# mimic1705.net
KiCad netlist of a schematic drawn in EAGLE
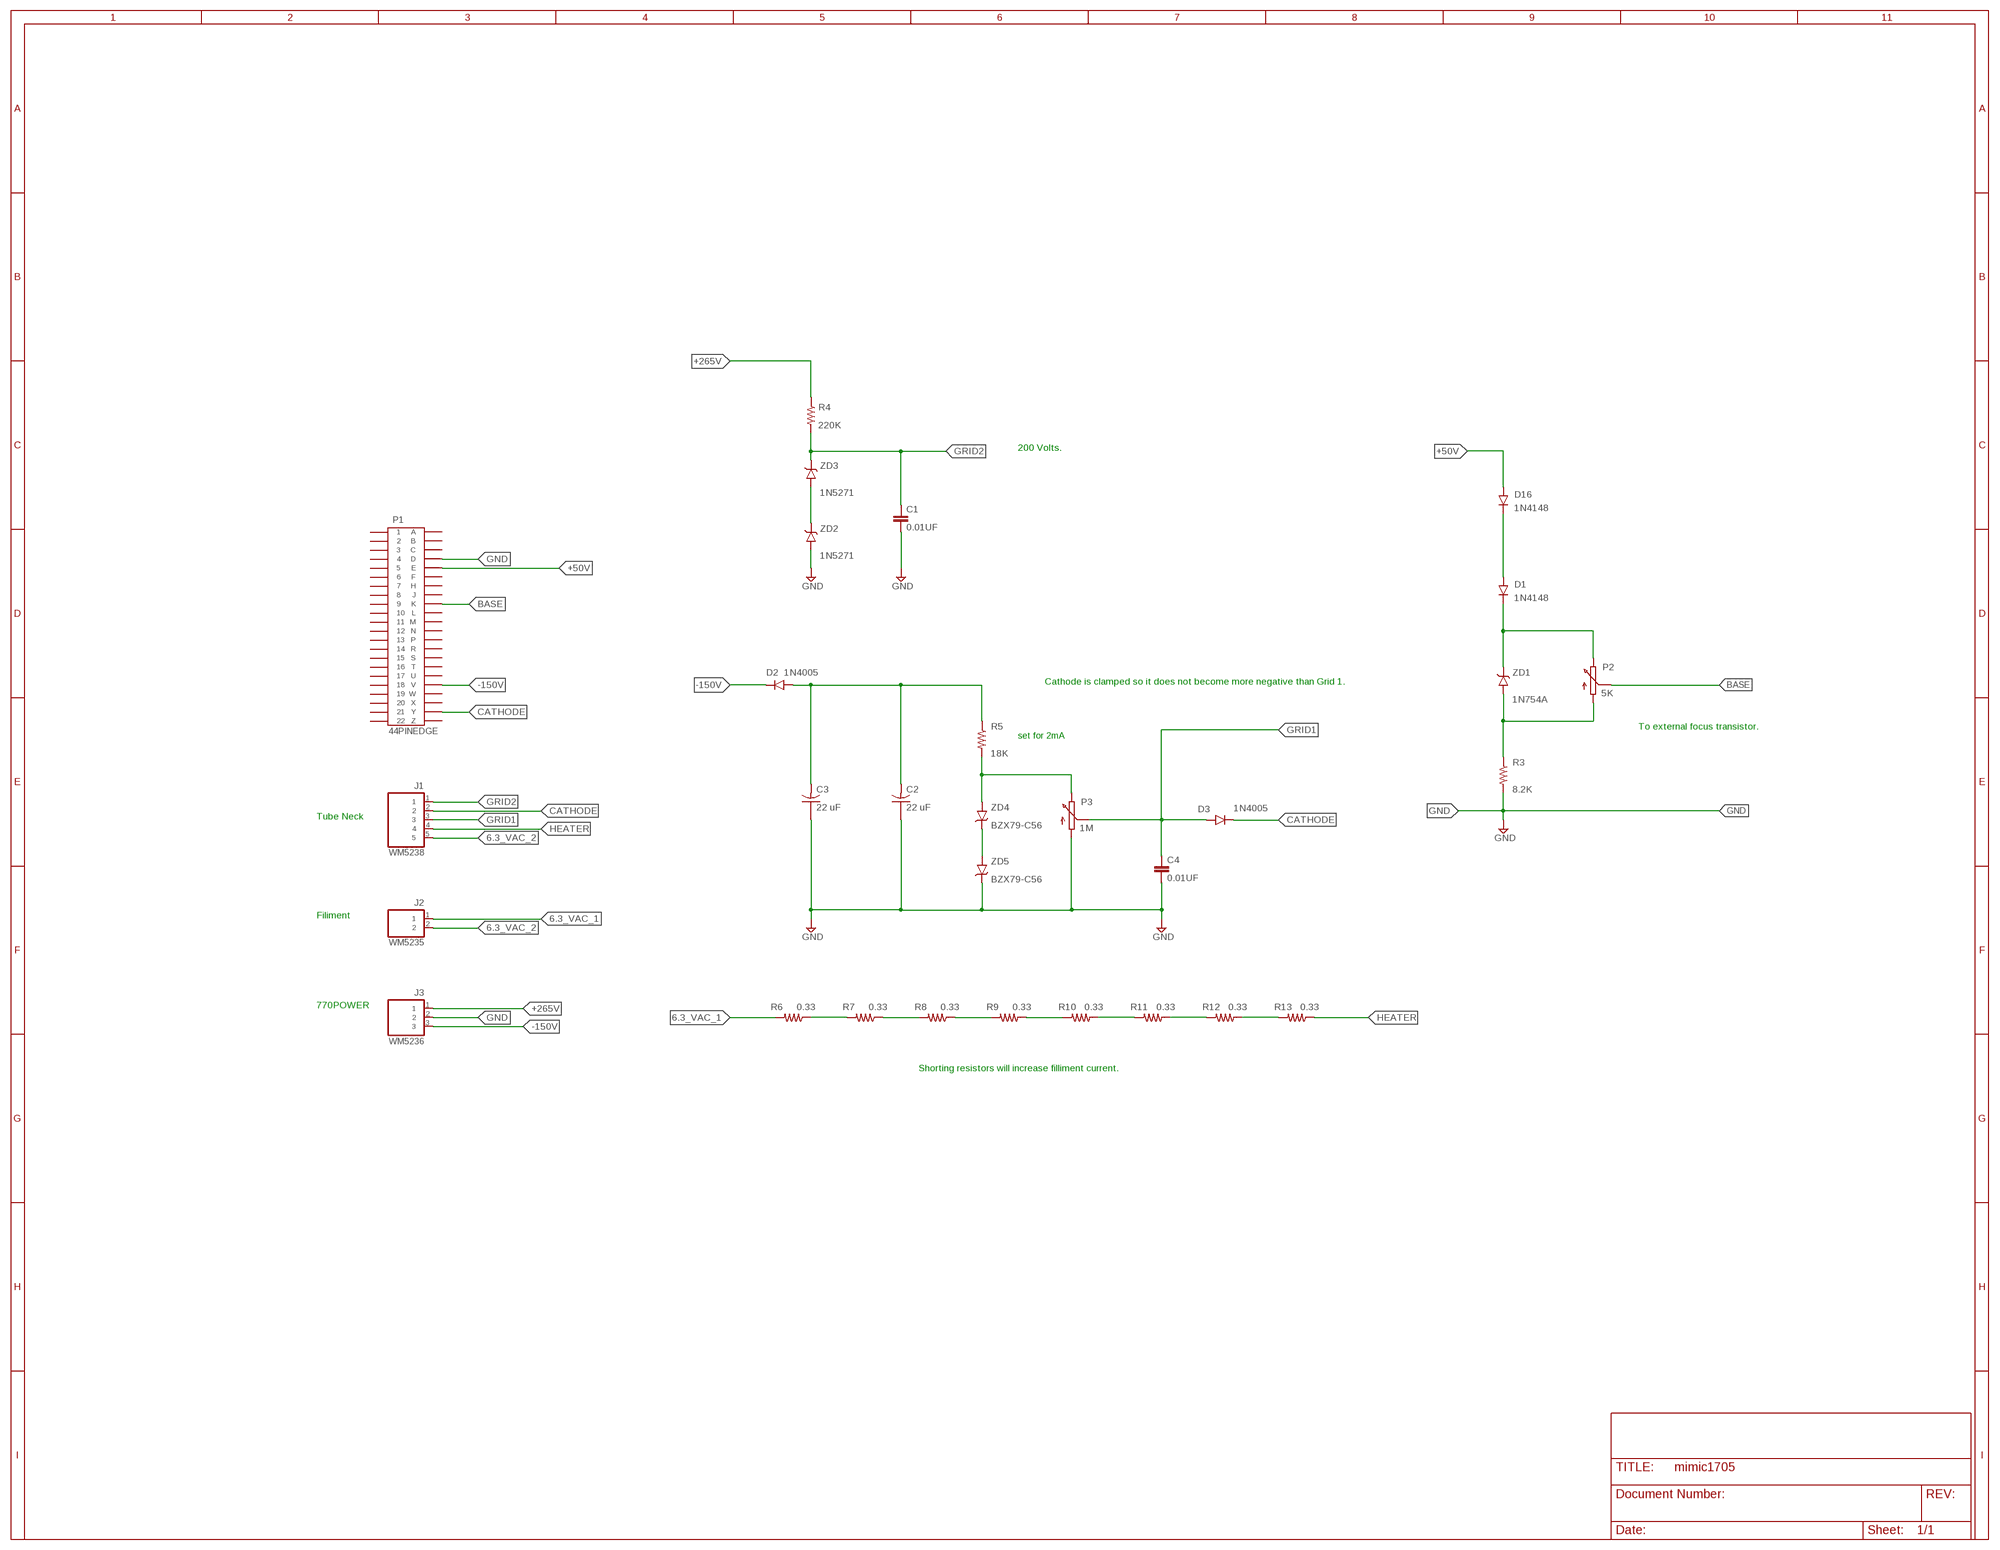
[diagram p0: schematic, sheet 1]

(export (version "E")
  (design (tool "Eeschema 10.0.6"))
  (components
    (comp (ref "C1")
      (value "0.01UF")
      (footprint "eagle-import:5MM_TH")
      (libsource (lib "eagle-import") (part "CAP_5MM"))
    )
    (comp (ref "C2")
      (value "22 uF")
      (footprint "eagle-import:AXIAL10X26")
      (libsource (lib "eagle-import") (part "CAP100UF200V"))
    )
    (comp (ref "C3")
      (value "22 uF")
      (footprint "eagle-import:AXIAL10X26")
      (libsource (lib "eagle-import") (part "CAP100UF200V"))
    )
    (comp (ref "C4")
      (value "0.01UF")
      (footprint "eagle-import:5MM_TH")
      (libsource (lib "eagle-import") (part "CAP_5MM"))
    )
    (comp (ref "D1")
      (value "1N4148")
      (footprint "eagle-import:DO35-7")
      (libsource (lib "eagle-import") (part "1N4148"))
    )
    (comp (ref "D2")
      (value "1N4005")
      (footprint "eagle-import:DO-41-10")
      (libsource (lib "eagle-import") (part "1N400X"))
    )
    (comp (ref "D3")
      (value "1N4005")
      (footprint "eagle-import:DO-41-10")
      (libsource (lib "eagle-import") (part "1N400X"))
    )
    (comp (ref "D16")
      (value "1N4148")
      (footprint "eagle-import:DO35-7")
      (libsource (lib "eagle-import") (part "1N4148"))
    )
    (comp (ref "J1")
      (value "WM5238")
      (footprint "eagle-import:MOLEX-WM5238")
      (libsource (lib "eagle-import") (part "WM5238"))
    )
    (comp (ref "J2")
      (value "WM5235")
      (footprint "eagle-import:MOLEX-WM5235")
      (libsource (lib "eagle-import") (part "WM5235"))
    )
    (comp (ref "J3")
      (value "WM5236")
      (footprint "eagle-import:MOLEX-WM5236")
      (libsource (lib "eagle-import") (part "WM5236"))
    )
    (comp (ref "P1")
      (value "44PINEDGE")
      (footprint "eagle-import:44PINEDGE")
      (libsource (lib "eagle-import") (part "44PINEDGE"))
    )
    (comp (ref "P2")
      (value "5K")
      (footprint "eagle-import:3006P")
      (libsource (lib "eagle-import") (part "POT-3006P"))
    )
    (comp (ref "P3")
      (value "1M")
      (footprint "eagle-import:3006P")
      (libsource (lib "eagle-import") (part "POT-3006P"))
    )
    (comp (ref "R3")
      (value "8.2K")
      (footprint "eagle-import:0207_10")
      (libsource (lib "eagle-import") (part "RES-V"))
    )
    (comp (ref "R4")
      (value "220K")
      (footprint "eagle-import:0207_10")
      (libsource (lib "eagle-import") (part "RES-V"))
    )
    (comp (ref "R5")
      (value "18K")
      (footprint "eagle-import:0207_10")
      (libsource (lib "eagle-import") (part "RES-V"))
    )
    (comp (ref "R6")
      (value "0.33")
      (footprint "eagle-import:0309_12")
      (libsource (lib "eagle-import") (part "R-1/2WATT"))
    )
    (comp (ref "R7")
      (value "0.33")
      (footprint "eagle-import:0309_12")
      (libsource (lib "eagle-import") (part "R-1/2WATT"))
    )
    (comp (ref "R8")
      (value "0.33")
      (footprint "eagle-import:0309_12")
      (libsource (lib "eagle-import") (part "R-1/2WATT"))
    )
    (comp (ref "R9")
      (value "0.33")
      (footprint "eagle-import:0309_12")
      (libsource (lib "eagle-import") (part "R-1/2WATT"))
    )
    (comp (ref "R10")
      (value "0.33")
      (footprint "eagle-import:0309_12")
      (libsource (lib "eagle-import") (part "R-1/2WATT"))
    )
    (comp (ref "R11")
      (value "0.33")
      (footprint "eagle-import:0309_12")
      (libsource (lib "eagle-import") (part "R-1/2WATT"))
    )
    (comp (ref "R12")
      (value "0.33")
      (footprint "eagle-import:0309_12")
      (libsource (lib "eagle-import") (part "R-1/2WATT"))
    )
    (comp (ref "R13")
      (value "0.33")
      (footprint "eagle-import:0309_12")
      (libsource (lib "eagle-import") (part "R-1/2WATT"))
    )
    (comp (ref "ZD1")
      (value "1N754A")
      (footprint "eagle-import:DO35-7")
      (libsource (lib "eagle-import") (part "1N754A"))
    )
    (comp (ref "ZD2")
      (value "1N5271")
      (footprint "eagle-import:DO35-7")
      (libsource (lib "eagle-import") (part "1N754A"))
    )
    (comp (ref "ZD3")
      (value "1N5271")
      (footprint "eagle-import:DO35-7")
      (libsource (lib "eagle-import") (part "1N754A"))
    )
    (comp (ref "ZD4")
      (value "BZX79-C56")
      (footprint "eagle-import:DO35-7")
      (libsource (lib "eagle-import") (part "1N754A"))
    )
    (comp (ref "ZD5")
      (value "BZX79-C56")
      (footprint "eagle-import:DO35-7")
      (libsource (lib "eagle-import") (part "1N754A"))
    )
  )
  (nets
    (net (code "1") (name "+50V") (class "Default")
      (node (ref "D16") (pin "A") (pinfunction "A_A") (pintype "passive"))
      (node (ref "P1") (pin "E") (pinfunction "E_E") (pintype "passive"))
    )
    (net (code "2") (name "+265V") (class "Default")
      (node (ref "J3") (pin "1") (pinfunction "1_1") (pintype "bidirectional"))
      (node (ref "R4") (pin "1") (pinfunction "P$1_1") (pintype "passive"))
    )
    (net (code "3") (name "-150V") (class "Default")
      (node (ref "D2") (pin "C") (pinfunction "C_C") (pintype "passive"))
      (node (ref "J3") (pin "3") (pinfunction "3_3") (pintype "bidirectional"))
      (node (ref "P1") (pin "V") (pinfunction "V_V") (pintype "passive"))
    )
    (net (code "4") (name "6.3_VAC_1") (class "Default")
      (node (ref "J2") (pin "1") (pinfunction "1_1") (pintype "bidirectional"))
      (node (ref "R6") (pin "2") (pinfunction "P$2_2") (pintype "passive"))
    )
    (net (code "5") (name "6.3_VAC_2") (class "Default")
      (node (ref "J1") (pin "5") (pinfunction "5_5") (pintype "bidirectional"))
      (node (ref "J2") (pin "2") (pinfunction "2_2") (pintype "bidirectional"))
    )
    (net (code "6") (name "BASE") (class "Default")
      (node (ref "P1") (pin "K") (pinfunction "K_K") (pintype "passive"))
      (node (ref "P2") (pin "2") (pinfunction "S_2") (pintype "passive"))
    )
    (net (code "7") (name "CATHODE") (class "Default")
      (node (ref "D3") (pin "C") (pinfunction "C_C") (pintype "passive"))
      (node (ref "J1") (pin "2") (pinfunction "2_2") (pintype "bidirectional"))
      (node (ref "P1") (pin "Y") (pinfunction "Y_Y") (pintype "passive"))
    )
    (net (code "8") (name "GND") (class "Default")
      (node (ref "C1") (pin "2") (pinfunction "2_2") (pintype "passive"))
      (node (ref "C2") (pin "P$1") (pinfunction "1_P$1") (pintype "passive"))
      (node (ref "C3") (pin "P$1") (pinfunction "1_P$1") (pintype "passive"))
      (node (ref "C4") (pin "2") (pinfunction "2_2") (pintype "passive"))
      (node (ref "J3") (pin "2") (pinfunction "2_2") (pintype "bidirectional"))
      (node (ref "P1") (pin "D") (pinfunction "D_D") (pintype "passive"))
      (node (ref "P3") (pin "1") (pinfunction "A_1") (pintype "passive"))
      (node (ref "R3") (pin "2") (pinfunction "P$2_2") (pintype "passive"))
      (node (ref "ZD2") (pin "A") (pinfunction "A_A") (pintype "passive"))
      (node (ref "ZD5") (pin "C") (pinfunction "C_C") (pintype "passive"))
    )
    (net (code "9") (name "GRID1") (class "Default")
      (node (ref "C4") (pin "1") (pinfunction "1_1") (pintype "passive"))
      (node (ref "D3") (pin "A") (pinfunction "A_A") (pintype "passive"))
      (node (ref "J1") (pin "3") (pinfunction "3_3") (pintype "bidirectional"))
      (node (ref "P3") (pin "2") (pinfunction "S_2") (pintype "passive"))
    )
    (net (code "10") (name "GRID2") (class "Default")
      (node (ref "C1") (pin "1") (pinfunction "1_1") (pintype "passive"))
      (node (ref "J1") (pin "1") (pinfunction "1_1") (pintype "bidirectional"))
      (node (ref "R4") (pin "2") (pinfunction "P$2_2") (pintype "passive"))
      (node (ref "ZD3") (pin "C") (pinfunction "C_C") (pintype "passive"))
    )
    (net (code "11") (name "HEATER") (class "Default")
      (node (ref "J1") (pin "4") (pinfunction "4_4") (pintype "bidirectional"))
      (node (ref "R13") (pin "1") (pinfunction "P$1_1") (pintype "passive"))
    )
    (net (code "12") (name "Net-(C2-2)") (class "Default")
      (node (ref "C2") (pin "P$2") (pinfunction "2_P$2") (pintype "passive"))
      (node (ref "C3") (pin "P$2") (pinfunction "2_P$2") (pintype "passive"))
      (node (ref "D2") (pin "A") (pinfunction "A_A") (pintype "passive"))
      (node (ref "R5") (pin "1") (pinfunction "P$1_1") (pintype "passive"))
    )
    (net (code "13") (name "Net-(D1-PadA)") (class "Default")
      (node (ref "D1") (pin "A") (pinfunction "A_A") (pintype "passive"))
      (node (ref "D16") (pin "C") (pinfunction "C_C") (pintype "passive"))
    )
    (net (code "14") (name "Net-(P2-A)") (class "Default")
      (node (ref "P2") (pin "1") (pinfunction "A_1") (pintype "passive"))
      (node (ref "R3") (pin "1") (pinfunction "P$1_1") (pintype "passive"))
      (node (ref "ZD1") (pin "A") (pinfunction "A_A") (pintype "passive"))
    )
    (net (code "15") (name "Net-(P2-E)") (class "Default")
      (node (ref "D1") (pin "C") (pinfunction "C_C") (pintype "passive"))
      (node (ref "P2") (pin "3") (pinfunction "E_3") (pintype "passive"))
      (node (ref "ZD1") (pin "C") (pinfunction "C_C") (pintype "passive"))
    )
    (net (code "16") (name "Net-(P3-E)") (class "Default")
      (node (ref "P3") (pin "3") (pinfunction "E_3") (pintype "passive"))
      (node (ref "R5") (pin "2") (pinfunction "P$2_2") (pintype "passive"))
      (node (ref "ZD4") (pin "A") (pinfunction "A_A") (pintype "passive"))
    )
    (net (code "17") (name "Net-(R6-P$1)") (class "Default")
      (node (ref "R6") (pin "1") (pinfunction "P$1_1") (pintype "passive"))
      (node (ref "R7") (pin "2") (pinfunction "P$2_2") (pintype "passive"))
    )
    (net (code "18") (name "Net-(R7-P$1)") (class "Default")
      (node (ref "R7") (pin "1") (pinfunction "P$1_1") (pintype "passive"))
      (node (ref "R8") (pin "2") (pinfunction "P$2_2") (pintype "passive"))
    )
    (net (code "19") (name "Net-(R8-P$1)") (class "Default")
      (node (ref "R8") (pin "1") (pinfunction "P$1_1") (pintype "passive"))
      (node (ref "R9") (pin "2") (pinfunction "P$2_2") (pintype "passive"))
    )
    (net (code "20") (name "Net-(R10-P$1)") (class "Default")
      (node (ref "R10") (pin "1") (pinfunction "P$1_1") (pintype "passive"))
      (node (ref "R11") (pin "2") (pinfunction "P$2_2") (pintype "passive"))
    )
    (net (code "21") (name "Net-(R10-P$2)") (class "Default")
      (node (ref "R10") (pin "2") (pinfunction "P$2_2") (pintype "passive"))
      (node (ref "R9") (pin "1") (pinfunction "P$1_1") (pintype "passive"))
    )
    (net (code "22") (name "Net-(R11-P$1)") (class "Default")
      (node (ref "R11") (pin "1") (pinfunction "P$1_1") (pintype "passive"))
      (node (ref "R12") (pin "2") (pinfunction "P$2_2") (pintype "passive"))
    )
    (net (code "23") (name "Net-(R12-P$1)") (class "Default")
      (node (ref "R12") (pin "1") (pinfunction "P$1_1") (pintype "passive"))
      (node (ref "R13") (pin "2") (pinfunction "P$2_2") (pintype "passive"))
    )
    (net (code "24") (name "Net-(ZD2-PadC)") (class "Default")
      (node (ref "ZD2") (pin "C") (pinfunction "C_C") (pintype "passive"))
      (node (ref "ZD3") (pin "A") (pinfunction "A_A") (pintype "passive"))
    )
    (net (code "25") (name "Net-(ZD4-PadC)") (class "Default")
      (node (ref "ZD4") (pin "C") (pinfunction "C_C") (pintype "passive"))
      (node (ref "ZD5") (pin "A") (pinfunction "A_A") (pintype "passive"))
    )
    (net (code "26") (name "unconnected-(P1-Pad1)") (class "Default")
      (node (ref "P1") (pin "1") (pinfunction "1_1") (pintype "passive"))
    )
    (net (code "27") (name "unconnected-(P1-Pad2)") (class "Default")
      (node (ref "P1") (pin "2") (pinfunction "2_2") (pintype "passive"))
    )
    (net (code "28") (name "unconnected-(P1-Pad3)") (class "Default")
      (node (ref "P1") (pin "3") (pinfunction "3_3") (pintype "passive"))
    )
    (net (code "29") (name "unconnected-(P1-Pad4)") (class "Default")
      (node (ref "P1") (pin "4") (pinfunction "4_4") (pintype "passive"))
    )
    (net (code "30") (name "unconnected-(P1-Pad5)") (class "Default")
      (node (ref "P1") (pin "5") (pinfunction "5_5") (pintype "passive"))
    )
    (net (code "31") (name "unconnected-(P1-Pad6)") (class "Default")
      (node (ref "P1") (pin "6") (pinfunction "6_6") (pintype "passive"))
    )
    (net (code "32") (name "unconnected-(P1-Pad7)") (class "Default")
      (node (ref "P1") (pin "7") (pinfunction "7_7") (pintype "passive"))
    )
    (net (code "33") (name "unconnected-(P1-Pad8)") (class "Default")
      (node (ref "P1") (pin "8") (pinfunction "8_8") (pintype "passive"))
    )
    (net (code "34") (name "unconnected-(P1-Pad9)") (class "Default")
      (node (ref "P1") (pin "9") (pinfunction "9_9") (pintype "passive"))
    )
    (net (code "35") (name "unconnected-(P1-Pad10)") (class "Default")
      (node (ref "P1") (pin "10") (pinfunction "10_10") (pintype "passive"))
    )
    (net (code "36") (name "unconnected-(P1-Pad11)") (class "Default")
      (node (ref "P1") (pin "11") (pinfunction "11_11") (pintype "passive"))
    )
    (net (code "37") (name "unconnected-(P1-Pad12)") (class "Default")
      (node (ref "P1") (pin "12") (pinfunction "12_12") (pintype "passive"))
    )
    (net (code "38") (name "unconnected-(P1-Pad13)") (class "Default")
      (node (ref "P1") (pin "13") (pinfunction "13_13") (pintype "passive"))
    )
    (net (code "39") (name "unconnected-(P1-Pad14)") (class "Default")
      (node (ref "P1") (pin "14") (pinfunction "14_14") (pintype "passive"))
    )
    (net (code "40") (name "unconnected-(P1-Pad15)") (class "Default")
      (node (ref "P1") (pin "15") (pinfunction "15_15") (pintype "passive"))
    )
    (net (code "41") (name "unconnected-(P1-Pad16)") (class "Default")
      (node (ref "P1") (pin "16") (pinfunction "16_16") (pintype "passive"))
    )
    (net (code "42") (name "unconnected-(P1-Pad17)") (class "Default")
      (node (ref "P1") (pin "17") (pinfunction "17_17") (pintype "passive"))
    )
    (net (code "43") (name "unconnected-(P1-Pad18)") (class "Default")
      (node (ref "P1") (pin "18") (pinfunction "18_18") (pintype "passive"))
    )
    (net (code "44") (name "unconnected-(P1-Pad19)") (class "Default")
      (node (ref "P1") (pin "19") (pinfunction "19_19") (pintype "passive"))
    )
    (net (code "45") (name "unconnected-(P1-Pad20)") (class "Default")
      (node (ref "P1") (pin "20") (pinfunction "20_20") (pintype "passive"))
    )
    (net (code "46") (name "unconnected-(P1-Pad21)") (class "Default")
      (node (ref "P1") (pin "21") (pinfunction "21_21") (pintype "passive"))
    )
    (net (code "47") (name "unconnected-(P1-Pad22)") (class "Default")
      (node (ref "P1") (pin "22") (pinfunction "22_22") (pintype "passive"))
    )
    (net (code "48") (name "unconnected-(P1-PadA)") (class "Default")
      (node (ref "P1") (pin "A") (pinfunction "A_A") (pintype "passive"))
    )
    (net (code "49") (name "unconnected-(P1-PadB)") (class "Default")
      (node (ref "P1") (pin "B") (pinfunction "B_B") (pintype "passive"))
    )
    (net (code "50") (name "unconnected-(P1-PadC)") (class "Default")
      (node (ref "P1") (pin "C") (pinfunction "C_C") (pintype "passive"))
    )
    (net (code "51") (name "unconnected-(P1-PadF)") (class "Default")
      (node (ref "P1") (pin "F") (pinfunction "F_F") (pintype "passive"))
    )
    (net (code "52") (name "unconnected-(P1-PadH)") (class "Default")
      (node (ref "P1") (pin "H") (pinfunction "H_H") (pintype "passive"))
    )
    (net (code "53") (name "unconnected-(P1-PadJ)") (class "Default")
      (node (ref "P1") (pin "J") (pinfunction "J_J") (pintype "passive"))
    )
    (net (code "54") (name "unconnected-(P1-PadL)") (class "Default")
      (node (ref "P1") (pin "L") (pinfunction "L_L") (pintype "passive"))
    )
    (net (code "55") (name "unconnected-(P1-PadM)") (class "Default")
      (node (ref "P1") (pin "M") (pinfunction "M_M") (pintype "passive"))
    )
    (net (code "56") (name "unconnected-(P1-PadN)") (class "Default")
      (node (ref "P1") (pin "N") (pinfunction "N_N") (pintype "passive"))
    )
    (net (code "57") (name "unconnected-(P1-PadP)") (class "Default")
      (node (ref "P1") (pin "P") (pinfunction "P_P") (pintype "passive"))
    )
    (net (code "58") (name "unconnected-(P1-PadR)") (class "Default")
      (node (ref "P1") (pin "R") (pinfunction "R_R") (pintype "passive"))
    )
    (net (code "59") (name "unconnected-(P1-PadS)") (class "Default")
      (node (ref "P1") (pin "S") (pinfunction "S_S") (pintype "passive"))
    )
    (net (code "60") (name "unconnected-(P1-PadT)") (class "Default")
      (node (ref "P1") (pin "T") (pinfunction "T_T") (pintype "passive"))
    )
    (net (code "61") (name "unconnected-(P1-PadU)") (class "Default")
      (node (ref "P1") (pin "U") (pinfunction "U_U") (pintype "passive"))
    )
    (net (code "62") (name "unconnected-(P1-PadW)") (class "Default")
      (node (ref "P1") (pin "W") (pinfunction "W_W") (pintype "passive"))
    )
    (net (code "63") (name "unconnected-(P1-PadX)") (class "Default")
      (node (ref "P1") (pin "X") (pinfunction "X_X") (pintype "passive"))
    )
    (net (code "64") (name "unconnected-(P1-PadZ)") (class "Default")
      (node (ref "P1") (pin "Z") (pinfunction "Z_Z") (pintype "passive"))
    )
  )
)
